# PCB_BLU3.net
KiCad netlist of a schematic drawn in Altium Designer
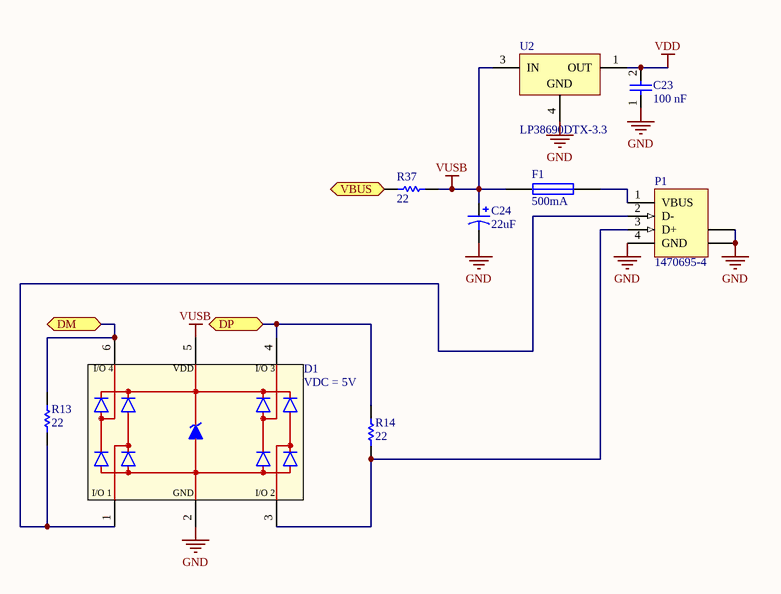
[diagram p0: PCB_BLU3.SchDoc]

(export (version "E")
  (design (tool "Eeschema 10.0.6"))
  (components
    (comp (ref "C23")
      (value "100 nF")
      (footprint "WCAP-CSGP 1206, H=0.8mm")
      (description "WCAP-CSGP MLCC, X7R, 1206, 100000 pF,10Vdc")
      (fields
        (field (name "MANUFACTURER") "Wurth Elektronik")
        (field (name "PARTNO") "885012208009")
        (field (name "E-MAIL") "libraries@we-online.com")
        (field (name "CREATED BY") "Karrer Zheng")
      )
      (libsource (lib "WCAP-CSGP_rev15b") (part "WCAP-CSGP 1206, 885012208009"))
    )
    (comp (ref "C24")
      (value "22uF")
      (footprint "6032")
      (fields (field (name "PUBLISHER") "Altium Limited"))
      (libsource (lib "Vishay Sprague Tantalum Chip Capacitor") (part "CWR11DH226M"))
    )
    (comp (ref "D1")
      (value "VDC = 5V")
      (footprint "SOT23-6L")
      (description "WE-TVS TVS Diode, High Speed Series, SOT23-6L, VDC = 5V")
      (fields
        (field (name "PARTNO") "824015")
        (field (name "MANUFACTURER") "Wurth Elektronik")
        (field (name "CREATED BY") "BJ.Chen")
      )
      (libsource (lib "WE-TVS_rev16a") (part "WE-TVS, SOT23-6L, 824015"))
    )
    (comp (ref "F1")
      (value "500mA")
      (footprint "RES2512R")
      (description "Fuse")
      (fields (field (name "PUBLISHER") "Altium Limited"))
      (libsource (lib "Miscellaneous Devices") (part "Fuse 1"))
    )
    (comp (ref "P1")
      (value "1470695-4")
      (footprint "1470695A")
      (description "USB 1.1, Right Angle, SMT, A Type, Plug, 4 Position, Black")
      (fields (field (name "PUBLISHER") "Altium Limited"))
      (libsource (lib "AMP Serial Bus USB") (part "1470695-4"))
    )
    (comp (ref "R13")
      (value "22")
      (footprint "RES0402R")
      (description "Resistor")
      (libsource (lib "PassiveSMT") (part "Resistor1"))
    )
    (comp (ref "R14")
      (value "22")
      (footprint "RES0402R")
      (description "Resistor")
      (libsource (lib "PassiveSMT") (part "Resistor1"))
    )
    (comp (ref "R37")
      (value "22")
      (footprint "RES0402R")
      (description "Resistor")
      (libsource (lib "PassiveSMT") (part "Resistor1"))
    )
    (comp (ref "U2")
      (value "LP38690DTX-3.3")
      (footprint "TD03B_N")
      (description "1A Low Dropout CMOS Linear Regulators Stable with Ceramic Output Capacitors, 3-pin TO-252")
      (fields (field (name "MANUFACTURER") "National Semiconductor"))
      (libsource (lib "National Semiconductor LDO") (part "LP38690DTX-3.3"))
    )
  )
  (nets
    (net (code "1") (name "/DM") (class "Default")
      (node (ref "D1") (pin "6") (pinfunction "I/O_4_6") (pintype "passive"))
      (node (ref "R13") (pin "2") (pinfunction "2_2") (pintype "passive"))
    )
    (net (code "2") (name "/DP") (class "Default")
      (node (ref "D1") (pin "4") (pinfunction "I/O_3_4") (pintype "passive"))
      (node (ref "R14") (pin "2") (pinfunction "2_2") (pintype "passive"))
    )
    (net (code "3") (name "/VBUS") (class "Default")
      (node (ref "R37") (pin "2") (pinfunction "2_2") (pintype "passive"))
    )
    (net (code "4") (name "GND") (class "Default")
      (node (ref "C23") (pin "1") (pinfunction "1_1") (pintype "passive"))
      (node (ref "C24") (pin "2") (pinfunction "2_2") (pintype "passive"))
      (node (ref "D1") (pin "2") (pinfunction "GND_2") (pintype "passive"))
      (node (ref "P1") (pin "4") (pinfunction "GND_4") (pintype "power_in"))
      (node (ref "P1") (pin "5") (pinfunction "SHLD_5") (pintype "passive"))
      (node (ref "P1") (pin "6") (pinfunction "SHLD_6") (pintype "passive"))
      (node (ref "U2") (pin "4") (pinfunction "GND_4") (pintype "power_in"))
    )
    (net (code "5") (name "Net-(D1-I{slash}O_1)") (class "Default")
      (node (ref "D1") (pin "1") (pinfunction "I/O_1_1") (pintype "passive"))
      (node (ref "P1") (pin "2") (pinfunction "D-_2") (pintype "input"))
      (node (ref "R13") (pin "1") (pinfunction "1_1") (pintype "passive"))
    )
    (net (code "6") (name "Net-(D1-I{slash}O_2)") (class "Default")
      (node (ref "D1") (pin "3") (pinfunction "I/O_2_3") (pintype "passive"))
      (node (ref "P1") (pin "3") (pinfunction "D+_3") (pintype "input"))
      (node (ref "R14") (pin "1") (pinfunction "1_1") (pintype "passive"))
    )
    (net (code "7") (name "Net-(P1-VBUS)") (class "Default")
      (node (ref "F1") (pin "2") (pinfunction "2_2") (pintype "passive"))
      (node (ref "P1") (pin "1") (pinfunction "VBUS_1") (pintype "power_in"))
    )
    (net (code "8") (name "VDD") (class "Default")
      (node (ref "C23") (pin "2") (pinfunction "2_2") (pintype "passive"))
      (node (ref "U2") (pin "1") (pinfunction "OUT_1") (pintype "power_in"))
    )
    (net (code "9") (name "VUSB") (class "Default")
      (node (ref "C24") (pin "1") (pinfunction "1_1") (pintype "passive"))
      (node (ref "D1") (pin "5") (pinfunction "VDD_5") (pintype "passive"))
      (node (ref "F1") (pin "1") (pinfunction "1_1") (pintype "passive"))
      (node (ref "R37") (pin "1") (pinfunction "1_1") (pintype "passive"))
      (node (ref "U2") (pin "3") (pinfunction "IN_3") (pintype "power_in"))
    )
  )
)
